# SkyKontrol-IotController.net
KiCad netlist of a schematic drawn in EAGLE
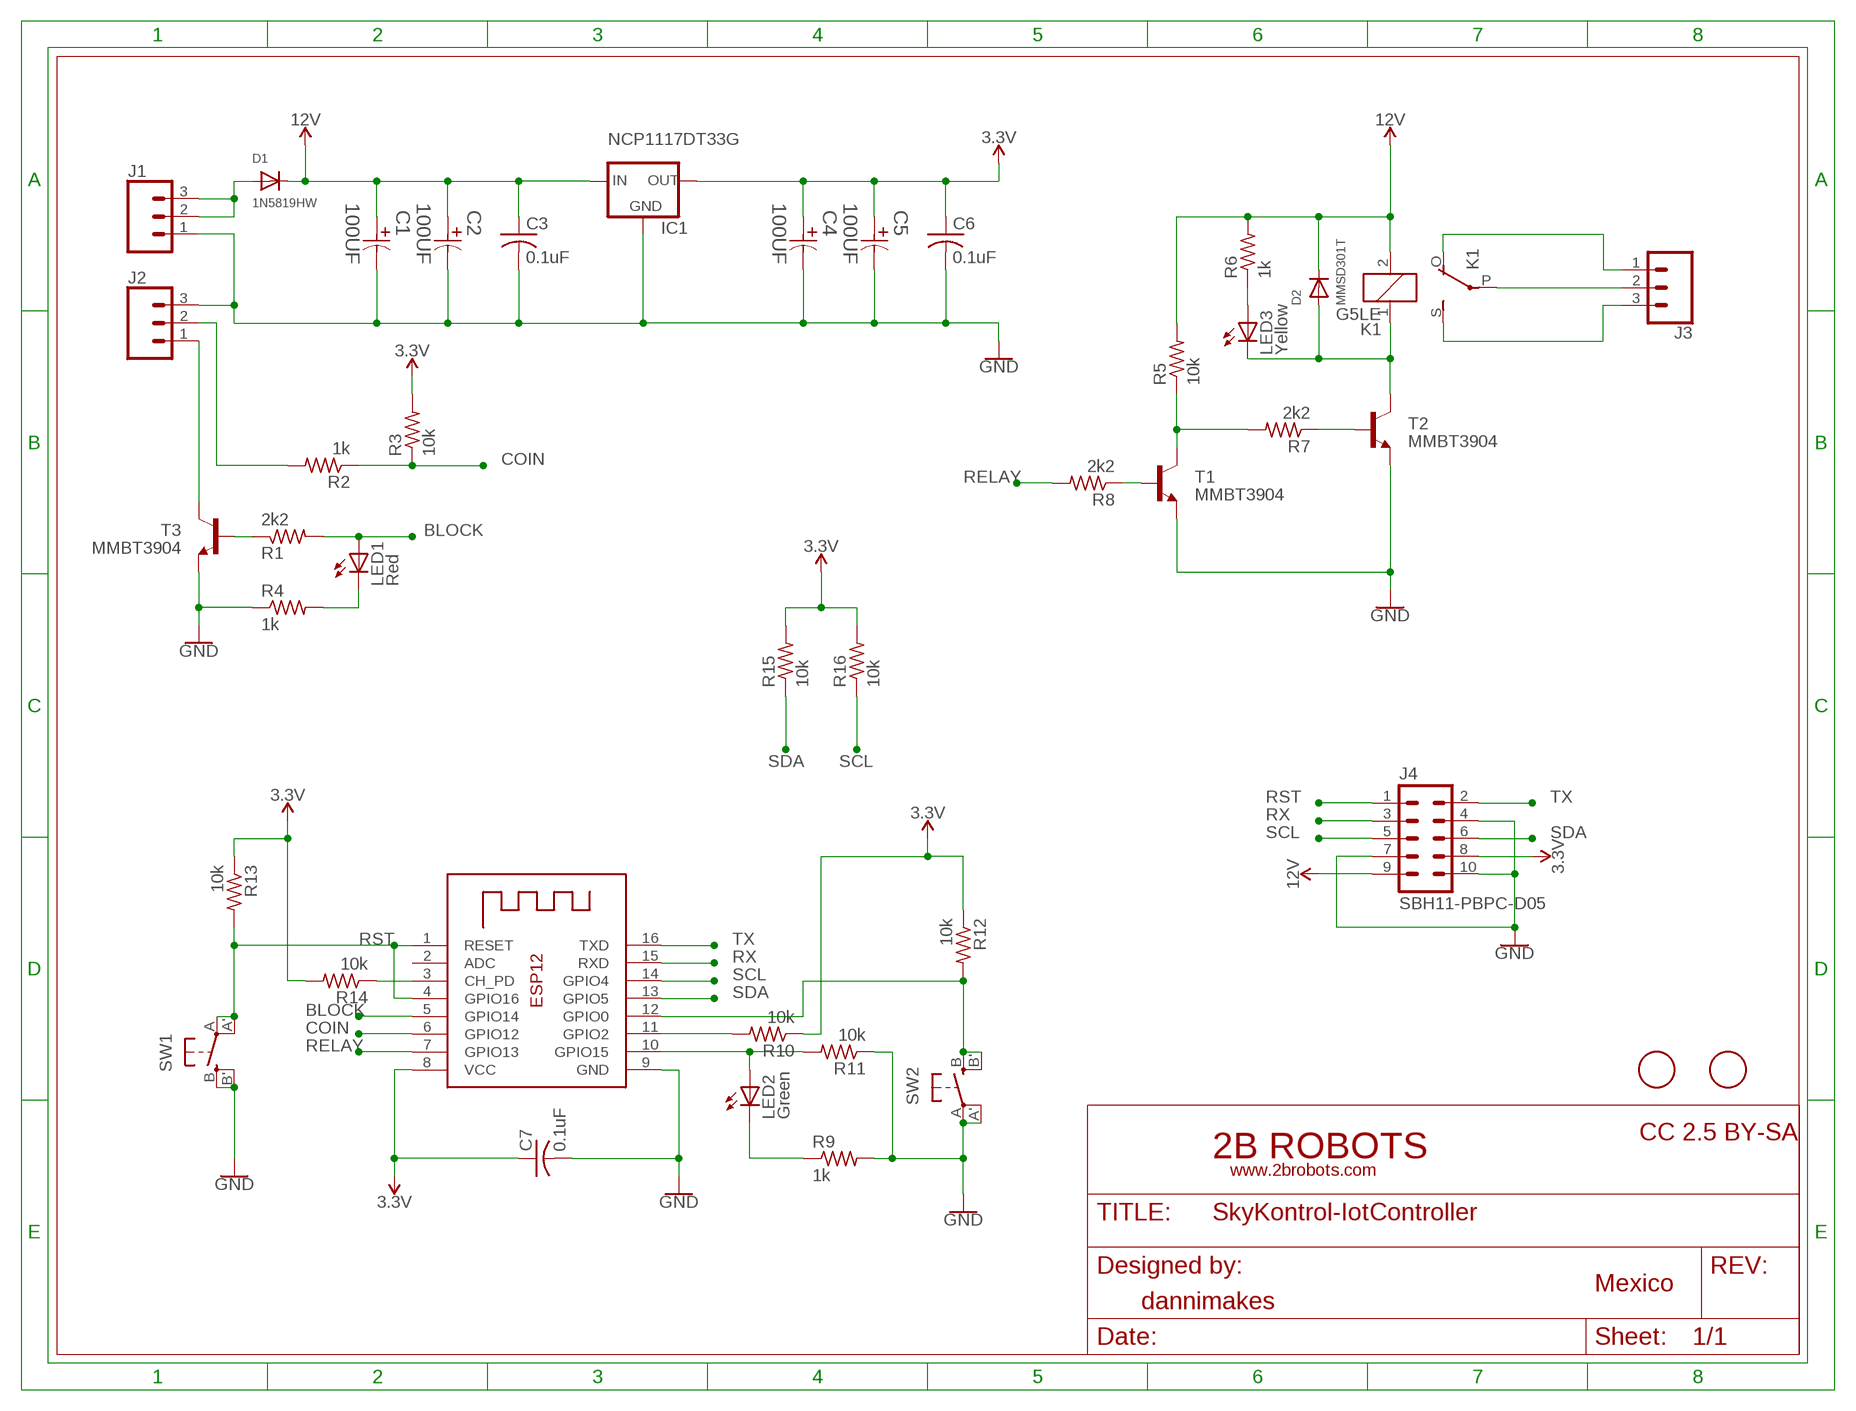
[diagram p0: schematic, sheet 1]

(export (version "E")
  (design (tool "Eeschema 10.0.6"))
  (components
    (comp (ref "C1")
      (value "100UF")
      (footprint "eagle-import:CAPAE660X800N")
      (fields (field (name "MPN") "EEE-HA1E101XP") (field (name "TOLERANCE") "±20 %"))
      (libsource (lib "eagle-import") (part "EEE--CASE-D8HA1E101XP"))
    )
    (comp (ref "C2")
      (value "100UF")
      (footprint "eagle-import:CAPAE660X800N")
      (fields (field (name "MPN") "EEE-HA1E101XP") (field (name "TOLERANCE") "±20 %"))
      (libsource (lib "eagle-import") (part "EEE--CASE-D8HA1E101XP"))
    )
    (comp (ref "C3")
      (value "0.1uF")
      (footprint "eagle-import:C0603K")
      (libsource (lib "eagle-import") (part "C-USC0603K"))
    )
    (comp (ref "C4")
      (value "100UF")
      (footprint "eagle-import:CAPAE660X800N")
      (fields (field (name "MPN") "EEE-HA1E101XP") (field (name "TOLERANCE") "±20 %"))
      (libsource (lib "eagle-import") (part "EEE--CASE-D8HA1E101XP"))
    )
    (comp (ref "C5")
      (value "100UF")
      (footprint "eagle-import:CAPAE660X800N")
      (fields (field (name "MPN") "EEE-HA1E101XP") (field (name "TOLERANCE") "±20 %"))
      (libsource (lib "eagle-import") (part "EEE--CASE-D8HA1E101XP"))
    )
    (comp (ref "C6")
      (value "0.1uF")
      (footprint "eagle-import:C0603K")
      (libsource (lib "eagle-import") (part "C-USC0603K"))
    )
    (comp (ref "C7")
      (value "0.1uF")
      (footprint "eagle-import:C0603K")
      (libsource (lib "eagle-import") (part "C-USC0603K"))
    )
    (comp (ref "D1")
      (value "1N5819HW")
      (footprint "eagle-import:SOD-123")
      (libsource (lib "eagle-import") (part "DIODESOD-123"))
    )
    (comp (ref "D2")
      (value "MMSD301T")
      (footprint "eagle-import:SOD-123")
      (libsource (lib "eagle-import") (part "DIODESOD-123"))
    )
    (comp (ref "IC1")
      (value "NCP1117DT33G")
      (footprint "eagle-import:TO252")
      (libsource (lib "eagle-import") (part "LM1117TO252"))
    )
    (comp (ref "J1")
      (value "CONN_03-SCREW-5MM")
      (footprint "eagle-import:SCREWTERMINAL-5MM-3")
      (libsource (lib "eagle-import") (part "CONN_03-SCREW-5MM"))
    )
    (comp (ref "J2")
      (value "CONN_03-SCREW-5MM")
      (footprint "eagle-import:SCREWTERMINAL-5MM-3")
      (libsource (lib "eagle-import") (part "CONN_03-SCREW-5MM"))
    )
    (comp (ref "J3")
      (value "CONN_03-SCREW-5MM")
      (footprint "eagle-import:SCREWTERMINAL-5MM-3")
      (libsource (lib "eagle-import") (part "CONN_03-SCREW-5MM"))
    )
    (comp (ref "J4")
      (value "SBH11-PBPC-D05")
      (footprint "eagle-import:SBH11-PBPC-D05")
      (libsource (lib "eagle-import") (part "SBH11-PBPC-D05"))
    )
    (comp (ref "K1")
      (value "G5LE")
      (footprint "eagle-import:G5LE")
      (libsource (lib "eagle-import") (part "G5LE"))
    )
    (comp (ref "LED1")
      (value "Red")
      (footprint "eagle-import:CHIPLED_1206")
      (libsource (lib "eagle-import") (part "LEDCHIPLED_1206"))
    )
    (comp (ref "LED2")
      (value "Green")
      (footprint "eagle-import:CHIPLED_1206")
      (libsource (lib "eagle-import") (part "LEDCHIPLED_1206"))
    )
    (comp (ref "LED3")
      (value "Yellow")
      (footprint "eagle-import:CHIPLED_1206")
      (libsource (lib "eagle-import") (part "LEDCHIPLED_1206"))
    )
    (comp (ref "R1")
      (value "2k2")
      (footprint "eagle-import:R0805")
      (libsource (lib "eagle-import") (part "R-US_R0805"))
    )
    (comp (ref "R2")
      (value "1k")
      (footprint "eagle-import:R0805")
      (libsource (lib "eagle-import") (part "R-US_R0805"))
    )
    (comp (ref "R3")
      (value "10k")
      (footprint "eagle-import:R0805")
      (libsource (lib "eagle-import") (part "R-US_R0805"))
    )
    (comp (ref "R4")
      (value "1k")
      (footprint "eagle-import:R0805")
      (libsource (lib "eagle-import") (part "R-US_R0805"))
    )
    (comp (ref "R5")
      (value "10k")
      (footprint "eagle-import:R0805")
      (libsource (lib "eagle-import") (part "R-US_R0805"))
    )
    (comp (ref "R6")
      (value "1k")
      (footprint "eagle-import:R0805")
      (libsource (lib "eagle-import") (part "R-US_R0805"))
    )
    (comp (ref "R7")
      (value "2k2")
      (footprint "eagle-import:R0805")
      (libsource (lib "eagle-import") (part "R-US_R0805"))
    )
    (comp (ref "R8")
      (value "2k2")
      (footprint "eagle-import:R0805")
      (libsource (lib "eagle-import") (part "R-US_R0805"))
    )
    (comp (ref "R9")
      (value "1k")
      (footprint "eagle-import:R0805")
      (libsource (lib "eagle-import") (part "R-US_R0805"))
    )
    (comp (ref "R10")
      (value "10k")
      (footprint "eagle-import:R0805")
      (libsource (lib "eagle-import") (part "R-US_R0805"))
    )
    (comp (ref "R11")
      (value "10k")
      (footprint "eagle-import:R0805")
      (libsource (lib "eagle-import") (part "R-US_R0805"))
    )
    (comp (ref "R12")
      (value "10k")
      (footprint "eagle-import:R0805")
      (libsource (lib "eagle-import") (part "R-US_R0805"))
    )
    (comp (ref "R13")
      (value "10k")
      (footprint "eagle-import:R0805")
      (libsource (lib "eagle-import") (part "R-US_R0805"))
    )
    (comp (ref "R14")
      (value "10k")
      (footprint "eagle-import:R0805")
      (libsource (lib "eagle-import") (part "R-US_R0805"))
    )
    (comp (ref "R15")
      (value "10k")
      (footprint "eagle-import:R0805")
      (libsource (lib "eagle-import") (part "R-US_R0805"))
    )
    (comp (ref "R16")
      (value "10k")
      (footprint "eagle-import:R0805")
      (libsource (lib "eagle-import") (part "R-US_R0805"))
    )
    (comp (ref "SW1")
      (value "SPST_TACT-EVQQ2")
      (footprint "eagle-import:EVQ-Q2")
      (libsource (lib "eagle-import") (part "SPST_TACT-EVQQ2"))
    )
    (comp (ref "SW2")
      (value "SPST_TACT-EVQQ2")
      (footprint "eagle-import:EVQ-Q2")
      (libsource (lib "eagle-import") (part "SPST_TACT-EVQQ2"))
    )
    (comp (ref "T1")
      (value "MMBT3904")
      (footprint "eagle-import:SOT23-BEC")
      (libsource (lib "eagle-import") (part "-NPN-SOT23-BECMMBT3904LT1"))
    )
    (comp (ref "T2")
      (value "MMBT3904")
      (footprint "eagle-import:SOT23-BEC")
      (libsource (lib "eagle-import") (part "-NPN-SOT23-BECMMBT3904LT1"))
    )
    (comp (ref "T3")
      (value "MMBT3904")
      (footprint "eagle-import:SOT23-BEC")
      (libsource (lib "eagle-import") (part "-NPN-SOT23-BECMMBT3904LT1"))
    )
    (comp (ref "U$1")
      (value "FIDUCIAL")
      (footprint "eagle-import:FIDUCIAL_1MM")
      (libsource (lib "eagle-import") (part "FIDUCIAL"))
    )
    (comp (ref "U$2")
      (value "FIDUCIAL")
      (footprint "eagle-import:FIDUCIAL_1MM")
      (libsource (lib "eagle-import") (part "FIDUCIAL"))
    )
    (comp (ref "X1")
      (value "ESP-12")
      (footprint "eagle-import:ESP-12")
      (libsource (lib "eagle-import") (part "ESP-12"))
    )
  )
  (nets
    (net (code "1") (name "/BLOCK") (class "Default")
      (node (ref "LED1") (pin "A") (pinfunction "A_A") (pintype "passive"))
      (node (ref "R1") (pin "2") (pinfunction "2_2") (pintype "passive"))
      (node (ref "X1") (pin "5") (pinfunction "GPIO14_5") (pintype "bidirectional"))
    )
    (net (code "2") (name "/COIN") (class "Default")
      (node (ref "R2") (pin "1") (pinfunction "1_1") (pintype "passive"))
      (node (ref "R3") (pin "1") (pinfunction "1_1") (pintype "passive"))
      (node (ref "X1") (pin "6") (pinfunction "GPIO12_6") (pintype "bidirectional"))
    )
    (net (code "3") (name "/RELAY") (class "Default")
      (node (ref "R8") (pin "2") (pinfunction "2_2") (pintype "passive"))
      (node (ref "X1") (pin "7") (pinfunction "GPIO13_7") (pintype "bidirectional"))
    )
    (net (code "4") (name "/RST") (class "Default")
      (node (ref "J4") (pin "1") (pinfunction "1_1") (pintype "passive"))
      (node (ref "R13") (pin "2") (pinfunction "2_2") (pintype "passive"))
      (node (ref "SW1") (pin "A") (pinfunction "P_A") (pintype "passive"))
      (node (ref "SW1") (pin "A'") (pinfunction "P1_A'") (pintype "passive"))
      (node (ref "X1") (pin "1") (pinfunction "RESET_1") (pintype "input"))
      (node (ref "X1") (pin "4") (pinfunction "GPIO16_4") (pintype "bidirectional"))
    )
    (net (code "5") (name "/RX") (class "Default")
      (node (ref "J4") (pin "3") (pinfunction "3_3") (pintype "passive"))
      (node (ref "X1") (pin "15") (pinfunction "RXD_15") (pintype "input"))
    )
    (net (code "6") (name "/SCL") (class "Default")
      (node (ref "J4") (pin "5") (pinfunction "5_5") (pintype "passive"))
      (node (ref "R16") (pin "1") (pinfunction "1_1") (pintype "passive"))
      (node (ref "X1") (pin "14") (pinfunction "GPIO4_14") (pintype "bidirectional"))
    )
    (net (code "7") (name "/SDA") (class "Default")
      (node (ref "J4") (pin "6") (pinfunction "6_6") (pintype "passive"))
      (node (ref "R15") (pin "1") (pinfunction "1_1") (pintype "passive"))
      (node (ref "X1") (pin "13") (pinfunction "GPIO5_13") (pintype "bidirectional"))
    )
    (net (code "8") (name "/TX") (class "Default")
      (node (ref "J4") (pin "2") (pinfunction "2_2") (pintype "passive"))
      (node (ref "X1") (pin "16") (pinfunction "TXD_16") (pintype "output"))
    )
    (net (code "9") (name "3.3V") (class "Default")
      (node (ref "C4") (pin "1") (pinfunction "1_1") (pintype "passive"))
      (node (ref "C5") (pin "1") (pinfunction "1_1") (pintype "passive"))
      (node (ref "C6") (pin "1") (pinfunction "1_1") (pintype "passive"))
      (node (ref "C7") (pin "1") (pinfunction "1_1") (pintype "passive"))
      (node (ref "IC1") (pin "3") (pinfunction "OUT_3") (pintype "passive"))
      (node (ref "J4") (pin "8") (pinfunction "8_8") (pintype "passive"))
      (node (ref "R10") (pin "1") (pinfunction "1_1") (pintype "passive"))
      (node (ref "R12") (pin "1") (pinfunction "1_1") (pintype "passive"))
      (node (ref "R13") (pin "1") (pinfunction "1_1") (pintype "passive"))
      (node (ref "R14") (pin "2") (pinfunction "2_2") (pintype "passive"))
      (node (ref "R15") (pin "2") (pinfunction "2_2") (pintype "passive"))
      (node (ref "R16") (pin "2") (pinfunction "2_2") (pintype "passive"))
      (node (ref "R3") (pin "2") (pinfunction "2_2") (pintype "passive"))
      (node (ref "X1") (pin "8") (pinfunction "VCC_8") (pintype "power_in"))
    )
    (net (code "10") (name "12V") (class "Default")
      (node (ref "C1") (pin "1") (pinfunction "1_1") (pintype "passive"))
      (node (ref "C2") (pin "1") (pinfunction "1_1") (pintype "passive"))
      (node (ref "C3") (pin "1") (pinfunction "1_1") (pintype "passive"))
      (node (ref "D1") (pin "C") (pinfunction "C_C") (pintype "passive"))
      (node (ref "D2") (pin "C") (pinfunction "C_C") (pintype "passive"))
      (node (ref "IC1") (pin "2") (pinfunction "IN_2") (pintype "input"))
      (node (ref "J4") (pin "9") (pinfunction "9_9") (pintype "passive"))
      (node (ref "K1") (pin "2") (pinfunction "2_2") (pintype "passive"))
      (node (ref "R5") (pin "2") (pinfunction "2_2") (pintype "passive"))
      (node (ref "R6") (pin "2") (pinfunction "2_2") (pintype "passive"))
    )
    (net (code "11") (name "GND") (class "Default")
      (node (ref "C1") (pin "2") (pinfunction "2_2") (pintype "passive"))
      (node (ref "C2") (pin "2") (pinfunction "2_2") (pintype "passive"))
      (node (ref "C3") (pin "2") (pinfunction "2_2") (pintype "passive"))
      (node (ref "C4") (pin "2") (pinfunction "2_2") (pintype "passive"))
      (node (ref "C5") (pin "2") (pinfunction "2_2") (pintype "passive"))
      (node (ref "C6") (pin "2") (pinfunction "2_2") (pintype "passive"))
      (node (ref "C7") (pin "2") (pinfunction "2_2") (pintype "passive"))
      (node (ref "IC1") (pin "1") (pinfunction "GND_1") (pintype "input"))
      (node (ref "J1") (pin "1") (pinfunction "1_1") (pintype "passive"))
      (node (ref "J2") (pin "3") (pinfunction "3_3") (pintype "passive"))
      (node (ref "J4") (pin "10") (pinfunction "10_10") (pintype "passive"))
      (node (ref "J4") (pin "4") (pinfunction "4_4") (pintype "passive"))
      (node (ref "J4") (pin "7") (pinfunction "7_7") (pintype "passive"))
      (node (ref "R11") (pin "1") (pinfunction "1_1") (pintype "passive"))
      (node (ref "R4") (pin "1") (pinfunction "1_1") (pintype "passive"))
      (node (ref "R9") (pin "2") (pinfunction "2_2") (pintype "passive"))
      (node (ref "SW1") (pin "B") (pinfunction "S_B") (pintype "passive"))
      (node (ref "SW1") (pin "B'") (pinfunction "S1_B'") (pintype "passive"))
      (node (ref "SW2") (pin "A") (pinfunction "P_A") (pintype "passive"))
      (node (ref "SW2") (pin "A'") (pinfunction "P1_A'") (pintype "passive"))
      (node (ref "T1") (pin "E") (pinfunction "E_E") (pintype "passive"))
      (node (ref "T2") (pin "E") (pinfunction "E_E") (pintype "passive"))
      (node (ref "T3") (pin "E") (pinfunction "E_E") (pintype "passive"))
      (node (ref "X1") (pin "9") (pinfunction "GND_9") (pintype "power_in"))
    )
    (net (code "12") (name "Net-(D1-PadA)") (class "Default")
      (node (ref "D1") (pin "A") (pinfunction "A_A") (pintype "passive"))
      (node (ref "J1") (pin "2") (pinfunction "2_2") (pintype "passive"))
      (node (ref "J1") (pin "3") (pinfunction "3_3") (pintype "passive"))
    )
    (net (code "13") (name "Net-(D2-PadA)") (class "Default")
      (node (ref "D2") (pin "A") (pinfunction "A_A") (pintype "passive"))
      (node (ref "K1") (pin "1") (pinfunction "1_1") (pintype "passive"))
      (node (ref "LED3") (pin "C") (pinfunction "C_C") (pintype "passive"))
      (node (ref "T2") (pin "C") (pinfunction "C_C") (pintype "passive"))
    )
    (net (code "14") (name "Net-(J2-Pad1)") (class "Default")
      (node (ref "J2") (pin "1") (pinfunction "1_1") (pintype "passive"))
      (node (ref "T3") (pin "C") (pinfunction "C_C") (pintype "passive"))
    )
    (net (code "15") (name "Net-(J2-Pad2)") (class "Default")
      (node (ref "J2") (pin "2") (pinfunction "2_2") (pintype "passive"))
      (node (ref "R2") (pin "2") (pinfunction "2_2") (pintype "passive"))
    )
    (net (code "16") (name "Net-(J3-Pad1)") (class "Default")
      (node (ref "J3") (pin "1") (pinfunction "1_1") (pintype "passive"))
      (node (ref "K1") (pin "O") (pinfunction "O_O") (pintype "passive"))
    )
    (net (code "17") (name "Net-(J3-Pad2)") (class "Default")
      (node (ref "J3") (pin "2") (pinfunction "2_2") (pintype "passive"))
      (node (ref "K1") (pin "P") (pinfunction "P_P") (pintype "passive"))
    )
    (net (code "18") (name "Net-(J3-Pad3)") (class "Default")
      (node (ref "J3") (pin "3") (pinfunction "3_3") (pintype "passive"))
      (node (ref "K1") (pin "S") (pinfunction "S_S") (pintype "passive"))
    )
    (net (code "19") (name "Net-(LED1-PadC)") (class "Default")
      (node (ref "LED1") (pin "C") (pinfunction "C_C") (pintype "passive"))
      (node (ref "R4") (pin "2") (pinfunction "2_2") (pintype "passive"))
    )
    (net (code "20") (name "Net-(LED2-PadC)") (class "Default")
      (node (ref "LED2") (pin "C") (pinfunction "C_C") (pintype "passive"))
      (node (ref "R9") (pin "1") (pinfunction "1_1") (pintype "passive"))
    )
    (net (code "21") (name "Net-(LED3-PadA)") (class "Default")
      (node (ref "LED3") (pin "A") (pinfunction "A_A") (pintype "passive"))
      (node (ref "R6") (pin "1") (pinfunction "1_1") (pintype "passive"))
    )
    (net (code "22") (name "Net-(R1-Pad1)") (class "Default")
      (node (ref "R1") (pin "1") (pinfunction "1_1") (pintype "passive"))
      (node (ref "T3") (pin "B") (pinfunction "B_B") (pintype "passive"))
    )
    (net (code "23") (name "Net-(R5-Pad1)") (class "Default")
      (node (ref "R5") (pin "1") (pinfunction "1_1") (pintype "passive"))
      (node (ref "R7") (pin "2") (pinfunction "2_2") (pintype "passive"))
      (node (ref "T1") (pin "C") (pinfunction "C_C") (pintype "passive"))
    )
    (net (code "24") (name "Net-(R7-Pad1)") (class "Default")
      (node (ref "R7") (pin "1") (pinfunction "1_1") (pintype "passive"))
      (node (ref "T2") (pin "B") (pinfunction "B_B") (pintype "passive"))
    )
    (net (code "25") (name "Net-(R8-Pad1)") (class "Default")
      (node (ref "R8") (pin "1") (pinfunction "1_1") (pintype "passive"))
      (node (ref "T1") (pin "B") (pinfunction "B_B") (pintype "passive"))
    )
    (net (code "26") (name "Net-(SW2-S)") (class "Default")
      (node (ref "R12") (pin "2") (pinfunction "2_2") (pintype "passive"))
      (node (ref "SW2") (pin "B") (pinfunction "S_B") (pintype "passive"))
      (node (ref "SW2") (pin "B'") (pinfunction "S1_B'") (pintype "passive"))
      (node (ref "X1") (pin "12") (pinfunction "GPIO0_12") (pintype "bidirectional"))
    )
    (net (code "27") (name "Net-(X1-CH_PD)") (class "Default")
      (node (ref "R14") (pin "1") (pinfunction "1_1") (pintype "passive"))
      (node (ref "X1") (pin "3") (pinfunction "CH_PD_3") (pintype "input"))
    )
    (net (code "28") (name "Net-(X1-GPIO2)") (class "Default")
      (node (ref "R10") (pin "2") (pinfunction "2_2") (pintype "passive"))
      (node (ref "X1") (pin "11") (pinfunction "GPIO2_11") (pintype "bidirectional"))
    )
    (net (code "29") (name "Net-(X1-GPIO15)") (class "Default")
      (node (ref "LED2") (pin "A") (pinfunction "A_A") (pintype "passive"))
      (node (ref "R11") (pin "2") (pinfunction "2_2") (pintype "passive"))
      (node (ref "X1") (pin "10") (pinfunction "GPIO15_10") (pintype "bidirectional"))
    )
    (net (code "30") (name "unconnected-(X1-ADC-Pad2)") (class "Default")
      (node (ref "X1") (pin "2") (pinfunction "ADC_2") (pintype "passive"))
    )
  )
)
